# MotorVSense.net
KiCad netlist of a schematic drawn in Altium Designer
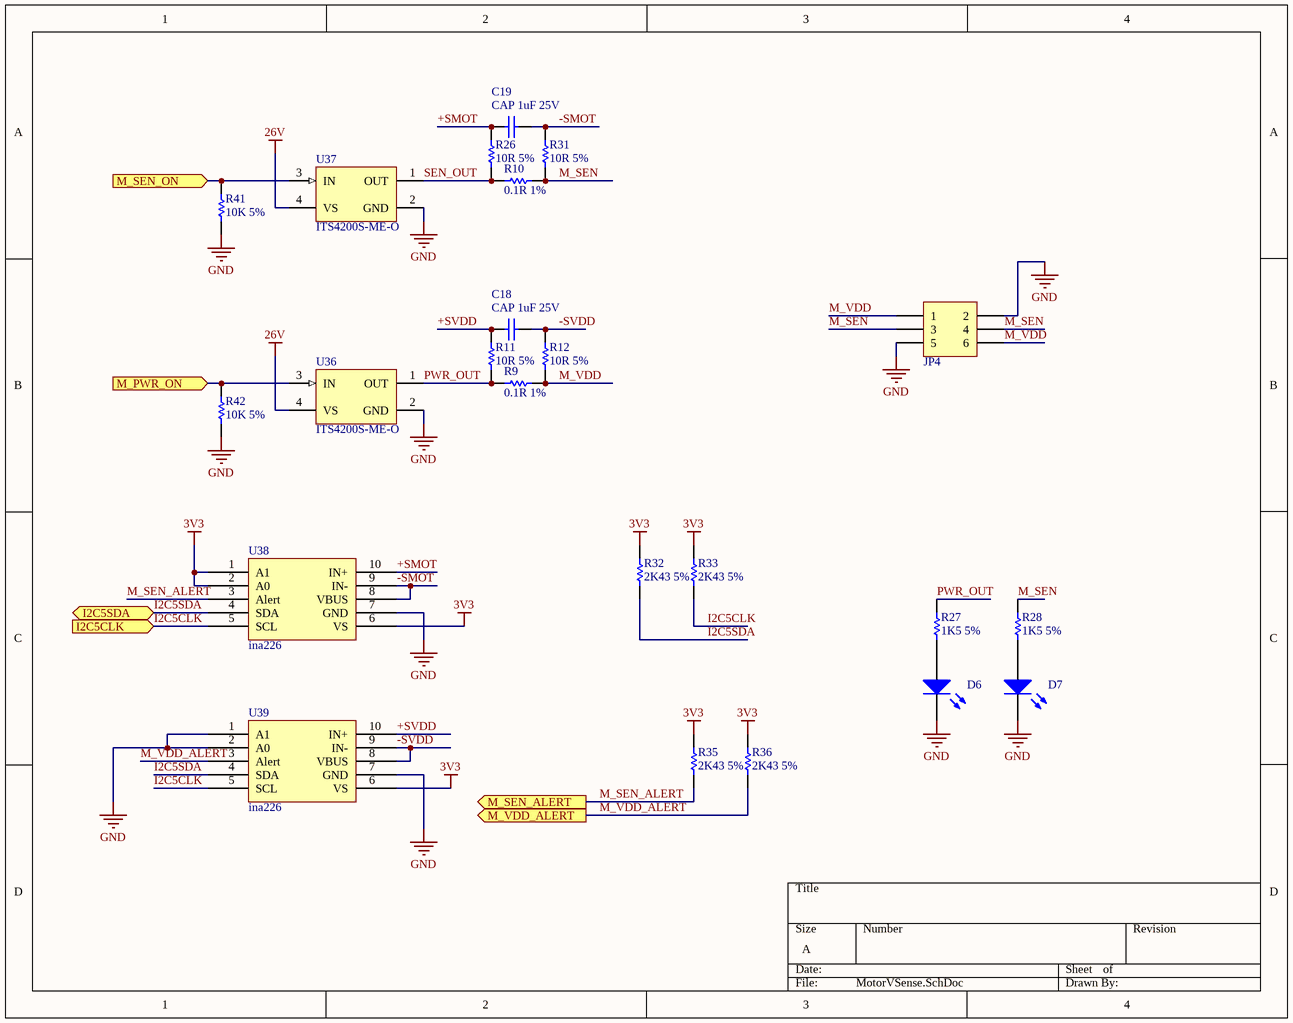
[diagram p0: MotorVSense.SchDoc]

(export (version "E")
  (design (tool "Eeschema 10.0.6"))
  (components
    (comp (ref "C18")
      (value "CAP 1uF 25V")
      (footprint "CAPC0603(1608)100_M")
      (description "CAP 1uF 25V Â±0.25pF 0603 (1608 Metric) Thickness 1mm SMD")
      (fields (field (name "TOLERANCE") "Â±0.25pF"))
      (libsource (lib "Altium Content Vault") (part "CMP-1035-00037-1"))
    )
    (comp (ref "C19")
      (value "CAP 1uF 25V")
      (footprint "CAPC0603(1608)100_M")
      (description "CAP 1uF 25V Â±0.25pF 0603 (1608 Metric) Thickness 1mm SMD")
      (fields (field (name "TOLERANCE") "Â±0.25pF"))
      (libsource (lib "Altium Content Vault") (part "CMP-1035-00037-1"))
    )
    (comp (ref "D6")
      (value "LED")
      (footprint "LED-0603")
      (description "Typical RED, GREEN, YELLOW, AMBER GaAs LED")
      (fields (field (name "PUBLISHER") "Altium Limited"))
      (libsource (lib "HSBNE-Vend") (part "LED"))
    )
    (comp (ref "D7")
      (value "LED")
      (footprint "LED-0603")
      (description "Typical RED, GREEN, YELLOW, AMBER GaAs LED")
      (fields (field (name "PUBLISHER") "Altium Limited"))
      (libsource (lib "HSBNE-Vend") (part "LED"))
    )
    (comp (ref "JP4")
      (value "Header 3x2 2.54mm")
      (footprint "2X3")
      (description "Header, 6-Pin")
      (libsource (lib "HSBNE-Vend") (part "Header 3x2"))
    )
    (comp (ref "R9")
      (value "0.1R 1%")
      (footprint "RESC2010(5025)_M")
      (description "0.1R 2010 1%")
      (fields (field (name "TOLERANCE") "None"))
      (libsource (lib "Altium Content Vault") (part "CMP-1017-00001-1"))
    )
    (comp (ref "R10")
      (value "0.1R 1%")
      (footprint "RESC2010(5025)_M")
      (description "0.1R 2010 1%")
      (fields (field (name "TOLERANCE") "None"))
      (libsource (lib "Altium Content Vault") (part "CMP-1017-00001-1"))
    )
    (comp (ref "R11")
      (value "10R 5%")
      (footprint "RESC0603(1608)_M")
      (description "10R 0.1W 5% 0603 (1608 Metric)  SMD")
      (fields (field (name "TOLERANCE") "5 %") (field (name "POWER") "0.1 W"))
      (libsource (lib "Altium Content Vault") (part "CMP-1012-00026-1"))
    )
    (comp (ref "R12")
      (value "10R 5%")
      (footprint "RESC0603(1608)_M")
      (description "10R 0.1W 5% 0603 (1608 Metric)  SMD")
      (fields (field (name "TOLERANCE") "5 %") (field (name "POWER") "0.1 W"))
      (libsource (lib "Altium Content Vault") (part "CMP-1012-00026-1"))
    )
    (comp (ref "R26")
      (value "10R 5%")
      (footprint "RESC0603(1608)_M")
      (description "10R 0.1W 5% 0603 (1608 Metric)  SMD")
      (fields (field (name "TOLERANCE") "5 %") (field (name "POWER") "0.1 W"))
      (libsource (lib "Altium Content Vault") (part "CMP-1012-00026-1"))
    )
    (comp (ref "R27")
      (value "1K5 5%")
      (footprint "RESC0603(1608)_M")
      (description "1K5 0.1W 5% 0603 (1608 Metric)  SMD")
      (fields (field (name "POWER") "0.1 W") (field (name "TOLERANCE") "5 %"))
      (libsource (lib "Altium Content Vault") (part "CMP-1012-00078-1"))
    )
    (comp (ref "R28")
      (value "1K5 5%")
      (footprint "RESC0603(1608)_M")
      (description "1K5 0.1W 5% 0603 (1608 Metric)  SMD")
      (fields (field (name "POWER") "0.1 W") (field (name "TOLERANCE") "5 %"))
      (libsource (lib "Altium Content Vault") (part "CMP-1012-00078-1"))
    )
    (comp (ref "R31")
      (value "10R 5%")
      (footprint "RESC0603(1608)_M")
      (description "10R 0.1W 5% 0603 (1608 Metric)  SMD")
      (fields (field (name "TOLERANCE") "5 %") (field (name "POWER") "0.1 W"))
      (libsource (lib "Altium Content Vault") (part "CMP-1012-00026-1"))
    )
    (comp (ref "R32")
      (value "2K43 5%")
      (footprint "RESC0603(1608)_M")
      (description "2K43 0.1W 5% 0603 (1608 Metric)  SMD")
      (fields (field (name "TOLERANCE") "5 %") (field (name "POWER") "0.1 W"))
      (libsource (lib "Altium Content Vault") (part "CMP-1012-00083-1"))
    )
    (comp (ref "R33")
      (value "2K43 5%")
      (footprint "RESC0603(1608)_M")
      (description "2K43 0.1W 5% 0603 (1608 Metric)  SMD")
      (fields (field (name "TOLERANCE") "5 %") (field (name "POWER") "0.1 W"))
      (libsource (lib "Altium Content Vault") (part "CMP-1012-00083-1"))
    )
    (comp (ref "R35")
      (value "2K43 5%")
      (footprint "RESC0603(1608)_M")
      (description "2K43 0.1W 5% 0603 (1608 Metric)  SMD")
      (fields (field (name "TOLERANCE") "5 %") (field (name "POWER") "0.1 W"))
      (libsource (lib "Altium Content Vault") (part "CMP-1012-00083-1"))
    )
    (comp (ref "R36")
      (value "2K43 5%")
      (footprint "RESC0603(1608)_M")
      (description "2K43 0.1W 5% 0603 (1608 Metric)  SMD")
      (fields (field (name "TOLERANCE") "5 %") (field (name "POWER") "0.1 W"))
      (libsource (lib "Altium Content Vault") (part "CMP-1012-00083-1"))
    )
    (comp (ref "R41")
      (value "10K 5%")
      (footprint "RESC0603(1608)_N")
      (description "10K 0.1W 5% 0603 (1608 Metric)  SMD")
      (fields (field (name "TOLERANCE") "5 %") (field (name "POWER") "0.1 W"))
      (libsource (lib "Altium Content Vault") (part "RES"))
    )
    (comp (ref "R42")
      (value "10K 5%")
      (footprint "RESC0603(1608)_M")
      (description "10K 0.1W 5% 0603 (1608 Metric)  SMD")
      (fields (field (name "TOLERANCE") "5 %") (field (name "POWER") "0.1 W"))
      (libsource (lib "Altium Content Vault") (part "CMP-1012-00098-1"))
    )
    (comp (ref "U36")
      (value "ITS4200S-ME-O")
      (footprint "INF-SOT223_M")
      (description "Smart High-Side NMOS-Power Switch, 11 to 45 V Operating, -40 to 125 degC, SOT223, Reel, Green")
      (fields (field (name "MANUFACTURER") "Infineon"))
      (libsource (lib "Altium Content Vault") (part "INF-ITS4200S-ME-X-SOT223-4"))
    )
    (comp (ref "U37")
      (value "ITS4200S-ME-O")
      (footprint "INF-SOT223_M")
      (description "Smart High-Side NMOS-Power Switch, 11 to 45 V Operating, -40 to 125 degC, SOT223, Reel, Green")
      (fields (field (name "MANUFACTURER") "Infineon"))
      (libsource (lib "Altium Content Vault") (part "INF-ITS4200S-ME-X-SOT223-4"))
    )
    (comp (ref "U38") (value "ina226") (footprint "SP10") (libsource (lib "HSBNE-Vend") (part "ina226")))
    (comp (ref "U39") (value "ina226") (footprint "SP10") (libsource (lib "HSBNE-Vend") (part "ina226")))
  )
  (nets
    (net (code "1") (name "/+SMOT") (class "Default")
      (node (ref "C19") (pin "2") (pinfunction "2_2") (pintype "passive"))
      (node (ref "R26") (pin "2") (pinfunction "2_2") (pintype "passive"))
      (node (ref "U38") (pin "10") (pinfunction "IN+_10") (pintype "passive"))
    )
    (net (code "2") (name "/+SVDD") (class "Default")
      (node (ref "C18") (pin "2") (pinfunction "2_2") (pintype "passive"))
      (node (ref "R11") (pin "2") (pinfunction "2_2") (pintype "passive"))
      (node (ref "U39") (pin "10") (pinfunction "IN+_10") (pintype "passive"))
    )
    (net (code "3") (name "/-SMOT") (class "Default")
      (node (ref "C19") (pin "1") (pinfunction "1_1") (pintype "passive"))
      (node (ref "R31") (pin "2") (pinfunction "2_2") (pintype "passive"))
      (node (ref "U38") (pin "8") (pinfunction "VBUS_8") (pintype "passive"))
      (node (ref "U38") (pin "9") (pinfunction "IN-_9") (pintype "passive"))
    )
    (net (code "4") (name "/-SVDD") (class "Default")
      (node (ref "C18") (pin "1") (pinfunction "1_1") (pintype "passive"))
      (node (ref "R12") (pin "2") (pinfunction "2_2") (pintype "passive"))
      (node (ref "U39") (pin "8") (pinfunction "VBUS_8") (pintype "passive"))
      (node (ref "U39") (pin "9") (pinfunction "IN-_9") (pintype "passive"))
    )
    (net (code "5") (name "/I2C5CLK") (class "Default")
      (node (ref "R33") (pin "1") (pinfunction "1_1") (pintype "passive"))
      (node (ref "U38") (pin "5") (pinfunction "SCL_5") (pintype "passive"))
      (node (ref "U39") (pin "5") (pinfunction "SCL_5") (pintype "passive"))
    )
    (net (code "6") (name "/I2C5SDA") (class "Default")
      (node (ref "R32") (pin "1") (pinfunction "1_1") (pintype "passive"))
      (node (ref "U38") (pin "4") (pinfunction "SDA_4") (pintype "passive"))
      (node (ref "U39") (pin "4") (pinfunction "SDA_4") (pintype "passive"))
    )
    (net (code "7") (name "/M_PWR_ON") (class "Default")
      (node (ref "R42") (pin "2") (pinfunction "2_2") (pintype "passive"))
      (node (ref "U36") (pin "3") (pinfunction "IN_3") (pintype "input"))
    )
    (net (code "8") (name "/M_SEN") (class "Default")
      (node (ref "JP4") (pin "3") (pinfunction "3_3") (pintype "passive"))
      (node (ref "JP4") (pin "4") (pinfunction "4_4") (pintype "passive"))
      (node (ref "R10") (pin "2") (pinfunction "2_2") (pintype "passive"))
      (node (ref "R28") (pin "2") (pinfunction "2_2") (pintype "passive"))
      (node (ref "R31") (pin "1") (pinfunction "1_1") (pintype "passive"))
    )
    (net (code "9") (name "/M_SEN_ALERT") (class "Default")
      (node (ref "R35") (pin "1") (pinfunction "1_1") (pintype "passive"))
      (node (ref "U38") (pin "3") (pinfunction "Alert_3") (pintype "passive"))
    )
    (net (code "10") (name "/M_SEN_ON") (class "Default")
      (node (ref "R41") (pin "2") (pinfunction "2_2") (pintype "passive"))
      (node (ref "U37") (pin "3") (pinfunction "IN_3") (pintype "input"))
    )
    (net (code "11") (name "/M_VDD") (class "Default")
      (node (ref "JP4") (pin "1") (pinfunction "1_1") (pintype "passive"))
      (node (ref "JP4") (pin "6") (pinfunction "6_6") (pintype "passive"))
      (node (ref "R12") (pin "1") (pinfunction "1_1") (pintype "passive"))
      (node (ref "R9") (pin "2") (pinfunction "2_2") (pintype "passive"))
    )
    (net (code "12") (name "/M_VDD_ALERT") (class "Default")
      (node (ref "R36") (pin "1") (pinfunction "1_1") (pintype "passive"))
      (node (ref "U39") (pin "3") (pinfunction "Alert_3") (pintype "passive"))
    )
    (net (code "13") (name "/PWR_OUT") (class "Default")
      (node (ref "R11") (pin "1") (pinfunction "1_1") (pintype "passive"))
      (node (ref "R27") (pin "2") (pinfunction "2_2") (pintype "passive"))
      (node (ref "R9") (pin "1") (pinfunction "1_1") (pintype "passive"))
      (node (ref "U36") (pin "1") (pinfunction "OUT_1") (pintype "power_in"))
    )
    (net (code "14") (name "/SEN_OUT") (class "Default")
      (node (ref "R10") (pin "1") (pinfunction "1_1") (pintype "passive"))
      (node (ref "R26") (pin "1") (pinfunction "1_1") (pintype "passive"))
      (node (ref "U37") (pin "1") (pinfunction "OUT_1") (pintype "power_in"))
    )
    (net (code "15") (name "3V3") (class "Default")
      (node (ref "R32") (pin "2") (pinfunction "2_2") (pintype "passive"))
      (node (ref "R33") (pin "2") (pinfunction "2_2") (pintype "passive"))
      (node (ref "R35") (pin "2") (pinfunction "2_2") (pintype "passive"))
      (node (ref "R36") (pin "2") (pinfunction "2_2") (pintype "passive"))
      (node (ref "U38") (pin "1") (pinfunction "A1_1") (pintype "passive"))
      (node (ref "U38") (pin "2") (pinfunction "A0_2") (pintype "passive"))
      (node (ref "U38") (pin "6") (pinfunction "VS_6") (pintype "passive"))
      (node (ref "U39") (pin "6") (pinfunction "VS_6") (pintype "passive"))
    )
    (net (code "16") (name "26V") (class "Default")
      (node (ref "U36") (pin "4") (pinfunction "VS_4") (pintype "power_in"))
      (node (ref "U37") (pin "4") (pinfunction "VS_4") (pintype "power_in"))
    )
    (net (code "17") (name "GND") (class "Default")
      (node (ref "D6") (pin "2") (pinfunction "K_2") (pintype "passive"))
      (node (ref "D7") (pin "2") (pinfunction "K_2") (pintype "passive"))
      (node (ref "JP4") (pin "2") (pinfunction "2_2") (pintype "passive"))
      (node (ref "JP4") (pin "5") (pinfunction "5_5") (pintype "passive"))
      (node (ref "R41") (pin "1") (pinfunction "1_1") (pintype "passive"))
      (node (ref "R42") (pin "1") (pinfunction "1_1") (pintype "passive"))
      (node (ref "U36") (pin "2") (pinfunction "GND_2") (pintype "power_in"))
      (node (ref "U37") (pin "2") (pinfunction "GND_2") (pintype "power_in"))
      (node (ref "U38") (pin "7") (pinfunction "GND_7") (pintype "passive"))
      (node (ref "U39") (pin "1") (pinfunction "A1_1") (pintype "passive"))
      (node (ref "U39") (pin "2") (pinfunction "A0_2") (pintype "passive"))
      (node (ref "U39") (pin "7") (pinfunction "GND_7") (pintype "passive"))
    )
    (net (code "18") (name "Net-(D6-A)") (class "Default")
      (node (ref "D6") (pin "1") (pinfunction "A_1") (pintype "passive"))
      (node (ref "R27") (pin "1") (pinfunction "1_1") (pintype "passive"))
    )
    (net (code "19") (name "Net-(D7-A)") (class "Default")
      (node (ref "D7") (pin "1") (pinfunction "A_1") (pintype "passive"))
      (node (ref "R28") (pin "1") (pinfunction "1_1") (pintype "passive"))
    )
  )
)
